# Myosense_v1.net
KiCad netlist of a schematic drawn in EAGLE
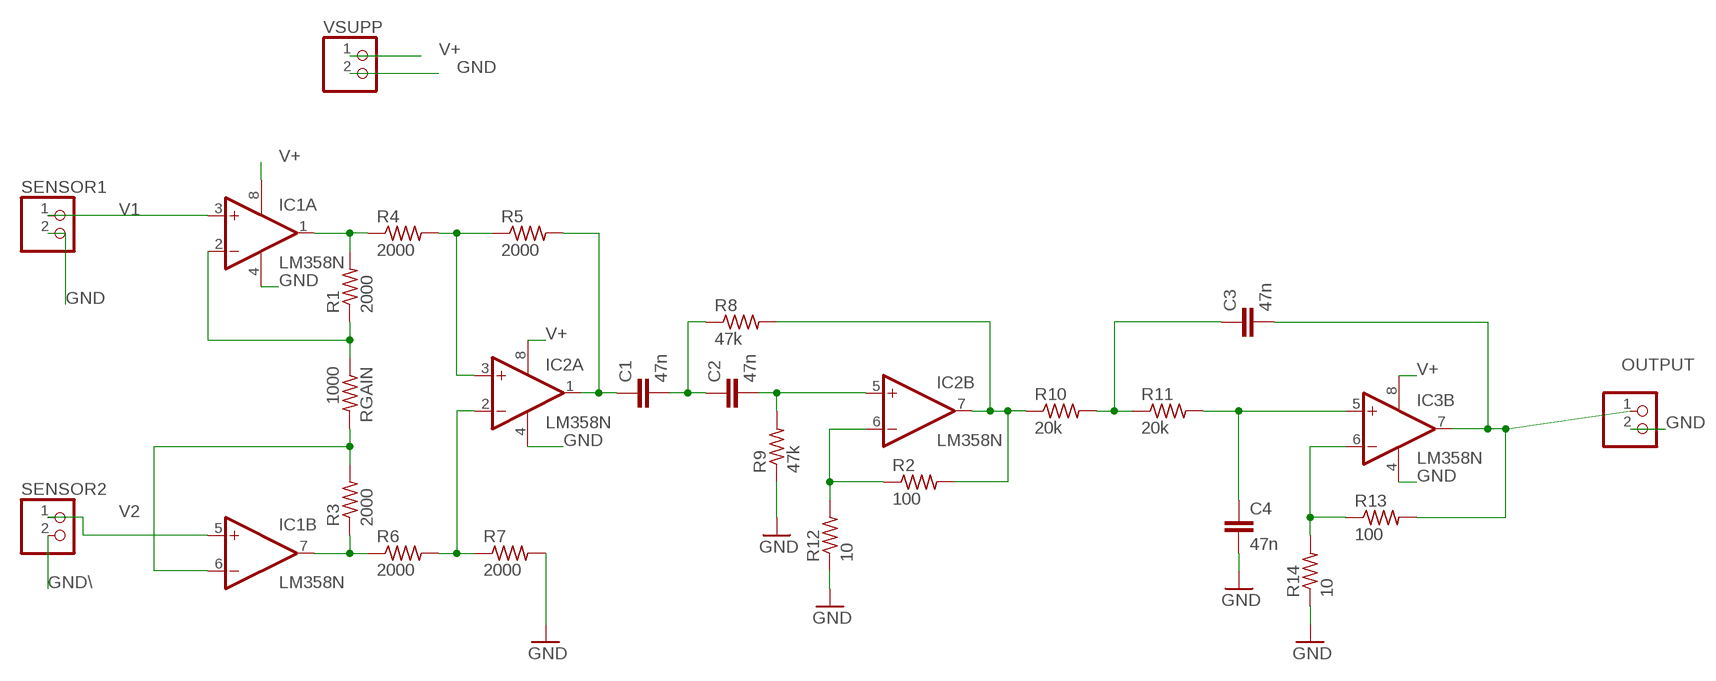
[diagram p0: schematic, sheet 1]

(export (version "E")
  (design (tool "Eeschema 10.0.6"))
  (components
    (comp (ref "C1")
      (value "47n")
      (footprint "eagle-import:C2.5-3")
      (libsource (lib "eagle-import") (part "C2,5-3"))
    )
    (comp (ref "C2")
      (value "47n")
      (footprint "eagle-import:C2.5-3")
      (libsource (lib "eagle-import") (part "C2,5-3"))
    )
    (comp (ref "C3")
      (value "47n")
      (footprint "eagle-import:C2.5-3")
      (libsource (lib "eagle-import") (part "C2,5-3"))
    )
    (comp (ref "C4")
      (value "47n")
      (footprint "eagle-import:C2.5-3")
      (libsource (lib "eagle-import") (part "C2,5-3"))
    )
    (comp (ref "IC1")
      (value "LM358N")
      (footprint "eagle-import:DIL08")
      (libsource (lib "eagle-import") (part "LM358N"))
    )
    (comp (ref "IC2")
      (value "LM358N")
      (footprint "eagle-import:DIL08")
      (libsource (lib "eagle-import") (part "LM358N"))
    )
    (comp (ref "IC3")
      (value "LM358N")
      (footprint "eagle-import:DIL08")
      (libsource (lib "eagle-import") (part "LM358N"))
    )
    (comp (ref "OUTPUT")
      (value "PINHD-1X2")
      (footprint "eagle-import:1X02")
      (libsource (lib "eagle-import") (part "PINHD-1X2"))
    )
    (comp (ref "R1")
      (value "2000")
      (footprint "eagle-import:0204_5")
      (libsource (lib "eagle-import") (part "R-US_0204/5"))
    )
    (comp (ref "R2")
      (value "100")
      (footprint "eagle-import:0204_5")
      (libsource (lib "eagle-import") (part "R-US_0204/5"))
    )
    (comp (ref "R3")
      (value "2000")
      (footprint "eagle-import:0204_5")
      (libsource (lib "eagle-import") (part "R-US_0204/5"))
    )
    (comp (ref "R4")
      (value "2000")
      (footprint "eagle-import:0204_5")
      (libsource (lib "eagle-import") (part "R-US_0204/5"))
    )
    (comp (ref "R5")
      (value "2000")
      (footprint "eagle-import:0204_5")
      (libsource (lib "eagle-import") (part "R-US_0204/5"))
    )
    (comp (ref "R6")
      (value "2000")
      (footprint "eagle-import:0204_5")
      (libsource (lib "eagle-import") (part "R-US_0204/5"))
    )
    (comp (ref "R7")
      (value "2000")
      (footprint "eagle-import:0204_5")
      (libsource (lib "eagle-import") (part "R-US_0204/5"))
    )
    (comp (ref "R8")
      (value "47k")
      (footprint "eagle-import:0204_5")
      (libsource (lib "eagle-import") (part "R-US_0204/5"))
    )
    (comp (ref "R9")
      (value "47k")
      (footprint "eagle-import:0204_5")
      (libsource (lib "eagle-import") (part "R-US_0204/5"))
    )
    (comp (ref "R10")
      (value "20k")
      (footprint "eagle-import:0204_5")
      (libsource (lib "eagle-import") (part "R-US_0204/5"))
    )
    (comp (ref "R11")
      (value "20k")
      (footprint "eagle-import:0204_5")
      (libsource (lib "eagle-import") (part "R-US_0204/5"))
    )
    (comp (ref "R12")
      (value "10")
      (footprint "eagle-import:0204_5")
      (libsource (lib "eagle-import") (part "R-US_0204/5"))
    )
    (comp (ref "R13")
      (value "100")
      (footprint "eagle-import:0204_5")
      (libsource (lib "eagle-import") (part "R-US_0204/5"))
    )
    (comp (ref "R14")
      (value "10")
      (footprint "eagle-import:0204_5")
      (libsource (lib "eagle-import") (part "R-US_0204/5"))
    )
    (comp (ref "RGAIN")
      (value "1000")
      (footprint "eagle-import:0204_5")
      (libsource (lib "eagle-import") (part "R-US_0204/5"))
    )
    (comp (ref "SENSOR1")
      (value "PINHD-1X2")
      (footprint "eagle-import:1X02")
      (libsource (lib "eagle-import") (part "pinhead_325_PINHD-1X2"))
    )
    (comp (ref "SENSOR2")
      (value "PINHD-1X2")
      (footprint "eagle-import:1X02")
      (libsource (lib "eagle-import") (part "pinhead_325_PINHD-1X2"))
    )
    (comp (ref "VSUPP")
      (value "PINHD-1X2")
      (footprint "eagle-import:1X02")
      (libsource (lib "eagle-import") (part "PINHD-1X2"))
    )
  )
  (nets
    (net (code "1") (name "/GND\\") (class "Default")
      (node (ref "SENSOR2") (pin "2") (pinfunction "2_2") (pintype "passive"))
    )
    (net (code "2") (name "/V+") (class "Default")
      (node (ref "IC1") (pin "8") (pinfunction "V+_8") (pintype "power_in"))
      (node (ref "IC2") (pin "8") (pinfunction "V+_8") (pintype "power_in"))
      (node (ref "IC3") (pin "8") (pinfunction "V+_8") (pintype "power_in"))
      (node (ref "VSUPP") (pin "1") (pinfunction "1_1") (pintype "passive"))
    )
    (net (code "3") (name "/V1") (class "Default")
      (node (ref "IC1") (pin "3") (pinfunction "+IN_3") (pintype "input"))
      (node (ref "SENSOR1") (pin "1") (pinfunction "1_1") (pintype "passive"))
    )
    (net (code "4") (name "/V2") (class "Default")
      (node (ref "IC1") (pin "5") (pinfunction "+IN_5") (pintype "input"))
      (node (ref "SENSOR2") (pin "1") (pinfunction "1_1") (pintype "passive"))
    )
    (net (code "5") (name "GND") (class "Default")
      (node (ref "C4") (pin "2") (pinfunction "2_2") (pintype "passive"))
      (node (ref "IC1") (pin "4") (pinfunction "V-_4") (pintype "power_in"))
      (node (ref "IC2") (pin "4") (pinfunction "V-_4") (pintype "power_in"))
      (node (ref "IC3") (pin "4") (pinfunction "V-_4") (pintype "power_in"))
      (node (ref "OUTPUT") (pin "2") (pinfunction "2_2") (pintype "passive"))
      (node (ref "R12") (pin "1") (pinfunction "1_1") (pintype "passive"))
      (node (ref "R14") (pin "1") (pinfunction "1_1") (pintype "passive"))
      (node (ref "R7") (pin "2") (pinfunction "2_2") (pintype "passive"))
      (node (ref "R9") (pin "1") (pinfunction "1_1") (pintype "passive"))
      (node (ref "SENSOR1") (pin "2") (pinfunction "2_2") (pintype "passive"))
      (node (ref "VSUPP") (pin "2") (pinfunction "2_2") (pintype "passive"))
    )
    (net (code "6") (name "Net-(C1-Pad2)") (class "Default")
      (node (ref "C1") (pin "2") (pinfunction "2_2") (pintype "passive"))
      (node (ref "C2") (pin "1") (pinfunction "1_1") (pintype "passive"))
      (node (ref "R8") (pin "1") (pinfunction "1_1") (pintype "passive"))
    )
    (net (code "7") (name "Net-(C3-Pad1)") (class "Default")
      (node (ref "C3") (pin "1") (pinfunction "1_1") (pintype "passive"))
      (node (ref "R10") (pin "2") (pinfunction "2_2") (pintype "passive"))
      (node (ref "R11") (pin "1") (pinfunction "1_1") (pintype "passive"))
    )
    (net (code "8") (name "Net-(IC1A--IN)") (class "Default")
      (node (ref "IC1") (pin "2") (pinfunction "-IN_2") (pintype "input"))
      (node (ref "R1") (pin "1") (pinfunction "1_1") (pintype "passive"))
      (node (ref "RGAIN") (pin "1") (pinfunction "1_1") (pintype "passive"))
    )
    (net (code "9") (name "Net-(IC1A-OUT)") (class "Default")
      (node (ref "IC1") (pin "1") (pinfunction "OUT_1") (pintype "output"))
      (node (ref "R1") (pin "2") (pinfunction "2_2") (pintype "passive"))
      (node (ref "R4") (pin "1") (pinfunction "1_1") (pintype "passive"))
    )
    (net (code "10") (name "Net-(IC1B--IN)") (class "Default")
      (node (ref "IC1") (pin "6") (pinfunction "-IN_6") (pintype "input"))
      (node (ref "R3") (pin "2") (pinfunction "2_2") (pintype "passive"))
      (node (ref "RGAIN") (pin "2") (pinfunction "2_2") (pintype "passive"))
    )
    (net (code "11") (name "Net-(IC1B-OUT)") (class "Default")
      (node (ref "IC1") (pin "7") (pinfunction "OUT_7") (pintype "output"))
      (node (ref "R3") (pin "1") (pinfunction "1_1") (pintype "passive"))
      (node (ref "R6") (pin "1") (pinfunction "1_1") (pintype "passive"))
    )
    (net (code "12") (name "Net-(IC2A-+IN)") (class "Default")
      (node (ref "IC2") (pin "3") (pinfunction "+IN_3") (pintype "input"))
      (node (ref "R4") (pin "2") (pinfunction "2_2") (pintype "passive"))
      (node (ref "R5") (pin "1") (pinfunction "1_1") (pintype "passive"))
    )
    (net (code "13") (name "Net-(IC2A--IN)") (class "Default")
      (node (ref "IC2") (pin "2") (pinfunction "-IN_2") (pintype "input"))
      (node (ref "R6") (pin "2") (pinfunction "2_2") (pintype "passive"))
      (node (ref "R7") (pin "1") (pinfunction "1_1") (pintype "passive"))
    )
    (net (code "14") (name "Net-(IC2A-OUT)") (class "Default")
      (node (ref "C1") (pin "1") (pinfunction "1_1") (pintype "passive"))
      (node (ref "IC2") (pin "1") (pinfunction "OUT_1") (pintype "output"))
      (node (ref "R5") (pin "2") (pinfunction "2_2") (pintype "passive"))
    )
    (net (code "15") (name "Net-(IC2B-+IN)") (class "Default")
      (node (ref "C2") (pin "2") (pinfunction "2_2") (pintype "passive"))
      (node (ref "IC2") (pin "5") (pinfunction "+IN_5") (pintype "input"))
      (node (ref "R9") (pin "2") (pinfunction "2_2") (pintype "passive"))
    )
    (net (code "16") (name "Net-(IC2B--IN)") (class "Default")
      (node (ref "IC2") (pin "6") (pinfunction "-IN_6") (pintype "input"))
      (node (ref "R12") (pin "2") (pinfunction "2_2") (pintype "passive"))
      (node (ref "R2") (pin "1") (pinfunction "1_1") (pintype "passive"))
    )
    (net (code "17") (name "Net-(IC2B-OUT)") (class "Default")
      (node (ref "IC2") (pin "7") (pinfunction "OUT_7") (pintype "output"))
      (node (ref "R10") (pin "1") (pinfunction "1_1") (pintype "passive"))
      (node (ref "R2") (pin "2") (pinfunction "2_2") (pintype "passive"))
      (node (ref "R8") (pin "2") (pinfunction "2_2") (pintype "passive"))
    )
    (net (code "18") (name "Net-(IC3B-+IN)") (class "Default")
      (node (ref "C4") (pin "1") (pinfunction "1_1") (pintype "passive"))
      (node (ref "IC3") (pin "5") (pinfunction "+IN_5") (pintype "input"))
      (node (ref "R11") (pin "2") (pinfunction "2_2") (pintype "passive"))
    )
    (net (code "19") (name "Net-(IC3B--IN)") (class "Default")
      (node (ref "IC3") (pin "6") (pinfunction "-IN_6") (pintype "input"))
      (node (ref "R13") (pin "1") (pinfunction "1_1") (pintype "passive"))
      (node (ref "R14") (pin "2") (pinfunction "2_2") (pintype "passive"))
    )
    (net (code "20") (name "Net-(IC3B-OUT)") (class "Default")
      (node (ref "C3") (pin "2") (pinfunction "2_2") (pintype "passive"))
      (node (ref "IC3") (pin "7") (pinfunction "OUT_7") (pintype "output"))
      (node (ref "OUTPUT") (pin "1") (pinfunction "1_1") (pintype "passive"))
      (node (ref "R13") (pin "2") (pinfunction "2_2") (pintype "passive"))
    )
  )
)
